# D5035-50.net
KiCad netlist of a schematic drawn in Altium Designer
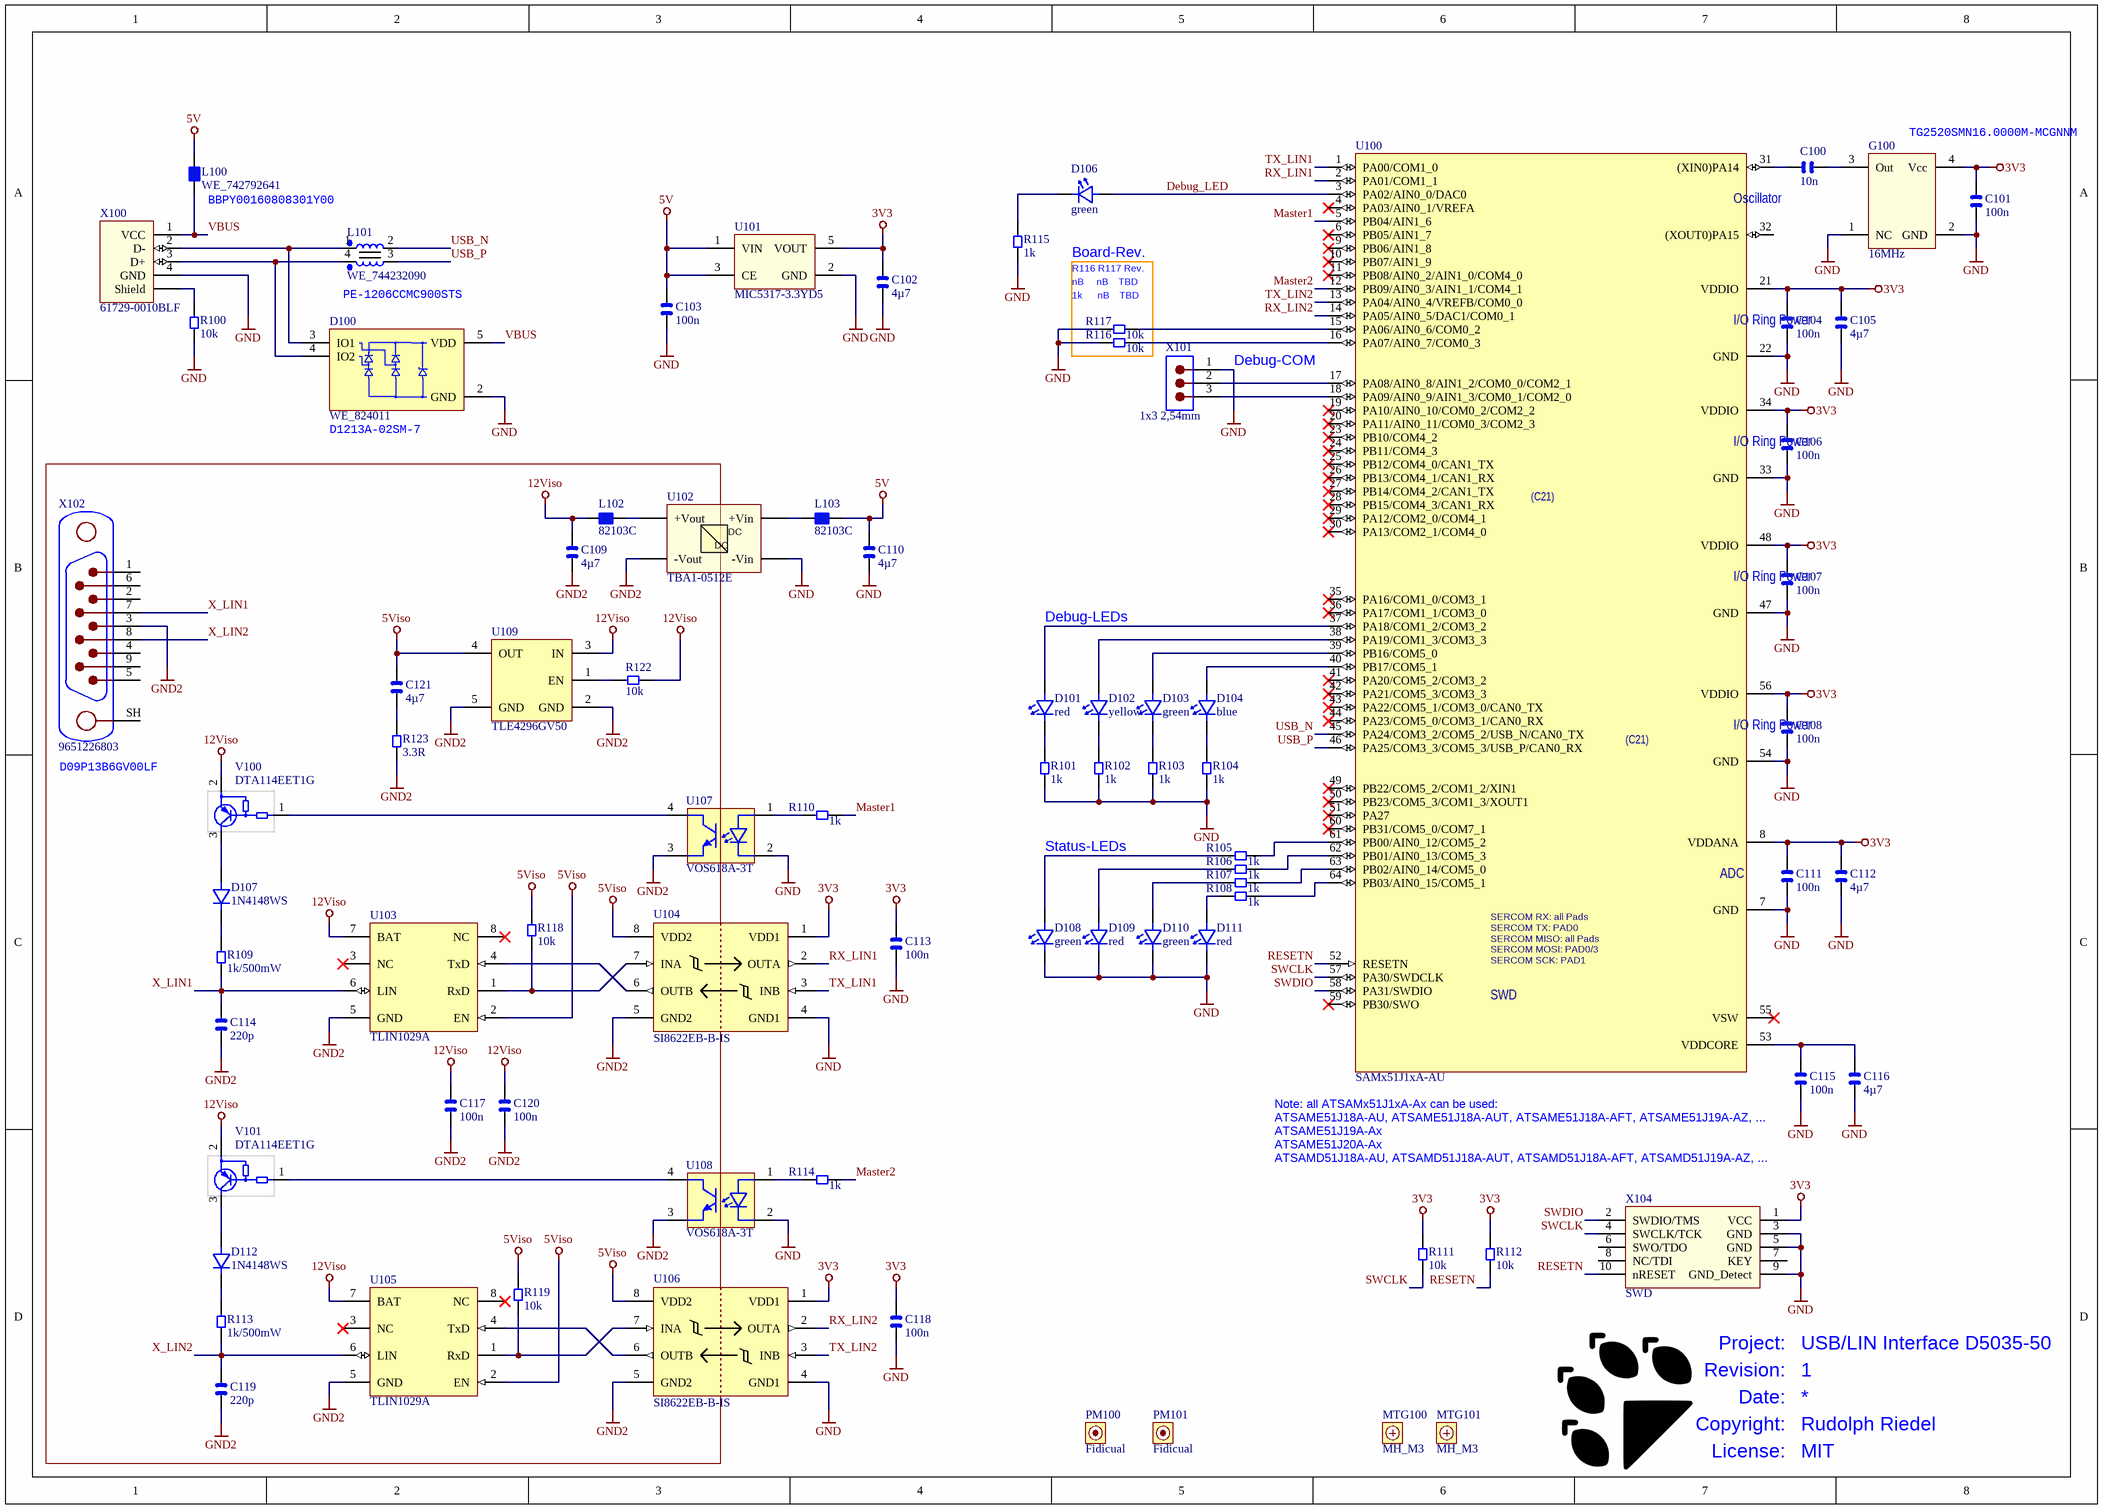
[diagram p0: D5035-50.SchDoc]

(export (version "E")
  (design (tool "Eeschema 10.0.6"))
  (components
    (comp (ref "C100")
      (value "10n")
      (footprint "CAPC1608X09L")
      (description "0603 Chip Capacitor")
      (fields (field (name "PART NUMBER") "CAPC_0603") (field (name "EDITOR") "rriedel"))
      (libsource (lib "HW-Labor_GF") (part "CAP_2_V2"))
    )
    (comp (ref "C101")
      (value "100n")
      (footprint "CAPC1608X09L")
      (description "0603 Chip Capacitor")
      (fields (field (name "PART NUMBER") "CAPC_0603") (field (name "EDITOR") "rriedel"))
      (libsource (lib "HW-Labor_GF") (part "CAP_2_V2"))
    )
    (comp (ref "C102")
      (value "4µ7")
      (footprint "CAPC2012X14L")
      (description "0805 Chip Capacitor")
      (fields (field (name "PART NUMBER") "CAPC_0805") (field (name "EDITOR") "rriedel"))
      (libsource (lib "HW-Labor_GF") (part "CAP_2_V2"))
    )
    (comp (ref "C103")
      (value "100n")
      (footprint "CAPC1608X09L")
      (description "0603 Chip Capacitor")
      (fields (field (name "PART NUMBER") "CAPC_0603") (field (name "EDITOR") "rriedel"))
      (libsource (lib "HW-Labor_GF") (part "CAP_2_V2"))
    )
    (comp (ref "C104")
      (value "100n")
      (footprint "CAPC1608X09L")
      (description "0603 Chip Capacitor")
      (fields (field (name "PART NUMBER") "CAPC_0603") (field (name "EDITOR") "rriedel"))
      (libsource (lib "HW-Labor_GF") (part "CAP_2_V2"))
    )
    (comp (ref "C105")
      (value "4µ7")
      (footprint "CAPC2012X14L")
      (description "0805 Chip Capacitor")
      (fields (field (name "PART NUMBER") "CAPC_0805") (field (name "EDITOR") "rriedel"))
      (libsource (lib "HW-Labor_GF") (part "CAP_2_V2"))
    )
    (comp (ref "C106")
      (value "100n")
      (footprint "CAPC1608X09L")
      (description "0603 Chip Capacitor")
      (fields (field (name "PART NUMBER") "CAPC_0603") (field (name "EDITOR") "rriedel"))
      (libsource (lib "HW-Labor_GF") (part "CAP_2_V2"))
    )
    (comp (ref "C107")
      (value "100n")
      (footprint "CAPC1608X09L")
      (description "0603 Chip Capacitor")
      (fields (field (name "PART NUMBER") "CAPC_0603") (field (name "EDITOR") "rriedel"))
      (libsource (lib "HW-Labor_GF") (part "CAP_2_V2"))
    )
    (comp (ref "C108")
      (value "100n")
      (footprint "CAPC1608X09L")
      (description "0603 Chip Capacitor")
      (fields (field (name "PART NUMBER") "CAPC_0603") (field (name "EDITOR") "rriedel"))
      (libsource (lib "HW-Labor_GF") (part "CAP_2_V2"))
    )
    (comp (ref "C109")
      (value "4µ7")
      (footprint "CAPC2012X14L")
      (description "0805 Chip Capacitor")
      (fields (field (name "PART NUMBER") "CAPC_0805") (field (name "EDITOR") "rriedel"))
      (libsource (lib "HW-Labor_GF") (part "CAP_2_V2"))
    )
    (comp (ref "C110")
      (value "4µ7")
      (footprint "CAPC2012X14L")
      (description "0805 Chip Capacitor")
      (fields (field (name "PART NUMBER") "CAPC_0805") (field (name "EDITOR") "rriedel"))
      (libsource (lib "HW-Labor_GF") (part "CAP_2_V2"))
    )
    (comp (ref "C111")
      (value "100n")
      (footprint "CAPC1608X09L")
      (description "0603 Chip Capacitor")
      (fields (field (name "PART NUMBER") "CAPC_0603") (field (name "EDITOR") "rriedel"))
      (libsource (lib "HW-Labor_GF") (part "CAP_2_V2"))
    )
    (comp (ref "C112")
      (value "4µ7")
      (footprint "CAPC2012X14L")
      (description "0805 Chip Capacitor")
      (fields (field (name "PART NUMBER") "CAPC_0805") (field (name "EDITOR") "rriedel"))
      (libsource (lib "HW-Labor_GF") (part "CAP_2_V2"))
    )
    (comp (ref "C113")
      (value "100n")
      (footprint "CAPC1608X09L")
      (description "0603 Chip Capacitor")
      (fields (field (name "PART NUMBER") "CAPC_0603") (field (name "EDITOR") "rriedel"))
      (libsource (lib "HW-Labor_GF") (part "CAP_2_V2"))
    )
    (comp (ref "C114")
      (value "220p")
      (footprint "CAPC2012X14L")
      (description "0805 Chip Capacitor")
      (fields (field (name "PART NUMBER") "CAPC_0805") (field (name "EDITOR") "rriedel"))
      (libsource (lib "HW-Labor_GF") (part "CAP_2_V2"))
    )
    (comp (ref "C115")
      (value "100n")
      (footprint "CAPC1608X09L")
      (description "0603 Chip Capacitor")
      (fields (field (name "PART NUMBER") "CAPC_0603") (field (name "EDITOR") "rriedel"))
      (libsource (lib "HW-Labor_GF") (part "CAP_2_V2"))
    )
    (comp (ref "C116")
      (value "4µ7")
      (footprint "CAPC2012X14L")
      (description "0805 Chip Capacitor")
      (fields (field (name "PART NUMBER") "CAPC_0805") (field (name "EDITOR") "rriedel"))
      (libsource (lib "HW-Labor_GF") (part "CAP_2_V2"))
    )
    (comp (ref "C117")
      (value "100n")
      (footprint "CAPC1608X09L")
      (description "0603 Chip Capacitor")
      (fields (field (name "PART NUMBER") "CAPC_0603") (field (name "EDITOR") "rriedel"))
      (libsource (lib "HW-Labor_GF") (part "CAP_2_V2"))
    )
    (comp (ref "C118")
      (value "100n")
      (footprint "CAPC1608X09L")
      (description "0603 Chip Capacitor")
      (fields (field (name "PART NUMBER") "CAPC_0603") (field (name "EDITOR") "rriedel"))
      (libsource (lib "HW-Labor_GF") (part "CAP_2_V2"))
    )
    (comp (ref "C119")
      (value "220p")
      (footprint "CAPC2012X14L")
      (description "0805 Chip Capacitor")
      (fields (field (name "PART NUMBER") "CAPC_0805") (field (name "EDITOR") "rriedel"))
      (libsource (lib "HW-Labor_GF") (part "CAP_2_V2"))
    )
    (comp (ref "C120")
      (value "100n")
      (footprint "CAPC1608X09L")
      (description "0603 Chip Capacitor")
      (fields (field (name "PART NUMBER") "CAPC_0603") (field (name "EDITOR") "rriedel"))
      (libsource (lib "HW-Labor_GF") (part "CAP_2_V2"))
    )
    (comp (ref "C121")
      (value "4µ7")
      (footprint "CAPC2012X14L")
      (description "0805 Chip Capacitor")
      (fields (field (name "PART NUMBER") "CAPC_0805") (field (name "EDITOR") "rriedel"))
      (libsource (lib "HW-Labor_GF") (part "CAP_2_V2"))
    )
    (comp (ref "D100")
      (value "WE_824011")
      (footprint "SOT95P280X110-5N")
      (description "TVS Diode Array WE-TVS")
      (fields
        (field (name "MANUFACTURER") "Wuerth")
        (field (name "DISTRIBUTOR_1_PART_NUMBER") "732-4465-1-ND")
        (field (name "EDITOR") "rriedel")
      )
      (libsource (lib "HW-Labor_GF") (part "WE-824011"))
    )
    (comp (ref "D101")
      (value "red")
      (footprint "DIOC1608X06N_LED")
      (description "LED, 0603")
      (fields (field (name "PART NUMBER") "LED_0603") (field (name "EDITOR") "rriedel"))
      (libsource (lib "HW-Labor_GF") (part "LED_generic"))
    )
    (comp (ref "D102")
      (value "yellow")
      (footprint "DIOC1608X06N_LED")
      (description "LED, 0603")
      (fields (field (name "PART NUMBER") "LED_0603") (field (name "EDITOR") "rriedel"))
      (libsource (lib "HW-Labor_GF") (part "LED_generic"))
    )
    (comp (ref "D103")
      (value "green")
      (footprint "DIOC1608X06N_LED")
      (description "LED, 0603")
      (fields (field (name "PART NUMBER") "LED_0603") (field (name "EDITOR") "rriedel"))
      (libsource (lib "HW-Labor_GF") (part "LED_generic"))
    )
    (comp (ref "D104")
      (value "blue")
      (footprint "DIOC1608X06N_LED")
      (description "LED, 0603")
      (fields (field (name "PART NUMBER") "LED_0603") (field (name "EDITOR") "rriedel"))
      (libsource (lib "HW-Labor_GF") (part "LED_generic"))
    )
    (comp (ref "D106")
      (value "green")
      (footprint "DIOC1608X06N_LED")
      (description "LED, 0603")
      (fields (field (name "PART NUMBER") "LED_0603") (field (name "EDITOR") "rriedel"))
      (libsource (lib "HW-Labor_GF") (part "LED_generic"))
    )
    (comp (ref "D107")
      (value "1N4148WS")
      (footprint "SOD323")
      (description "Small Signal Diode IF 0.15A, VR 75V, SOD323F")
      (fields (field (name "DISTRIBUTOR_1_PART_NUMBER") "C2128") (field (name "EDITOR") "rriedel"))
      (libsource (lib "HW-Labor_GF") (part "Diode_A2_K1"))
    )
    (comp (ref "D108")
      (value "green")
      (footprint "DIOC1608X06N_LED")
      (description "LED, 0603")
      (fields (field (name "PART NUMBER") "LED_0603") (field (name "EDITOR") "rriedel"))
      (libsource (lib "HW-Labor_GF") (part "LED_generic"))
    )
    (comp (ref "D109")
      (value "red")
      (footprint "DIOC1608X06N_LED")
      (description "LED, 0603")
      (fields (field (name "PART NUMBER") "LED_0603") (field (name "EDITOR") "rriedel"))
      (libsource (lib "HW-Labor_GF") (part "LED_generic"))
    )
    (comp (ref "D110")
      (value "green")
      (footprint "DIOC1608X06N_LED")
      (description "LED, 0603")
      (fields (field (name "PART NUMBER") "LED_0603") (field (name "EDITOR") "rriedel"))
      (libsource (lib "HW-Labor_GF") (part "LED_generic"))
    )
    (comp (ref "D111")
      (value "red")
      (footprint "DIOC1608X06N_LED")
      (description "LED, 0603")
      (fields (field (name "PART NUMBER") "LED_0603") (field (name "EDITOR") "rriedel"))
      (libsource (lib "HW-Labor_GF") (part "LED_generic"))
    )
    (comp (ref "D112")
      (value "1N4148WS")
      (footprint "SOD323")
      (description "Small Signal Diode IF 0.15A, VR 75V, SOD323F")
      (fields (field (name "DISTRIBUTOR_1_PART_NUMBER") "C2128") (field (name "EDITOR") "rriedel"))
      (libsource (lib "HW-Labor_GF") (part "Diode_A2_K1"))
    )
    (comp (ref "G100")
      (value "16MHz")
      (footprint "TG2520")
      (description "16MHz Oscillator, +/- 0.5ppm")
      (fields
        (field (name "PART NUMBER") "TG2520SMN16.0000M-MCGNNM")
        (field (name "MANUFACTURER") "Epson")
        (field (name "EDITOR") "rriedel")
      )
      (libsource (lib "HW-Labor_GF") (part "TG2520"))
    )
    (comp (ref "L100")
      (value "WE_742792641")
      (footprint "INDC1608X06L")
      (description "SMT EMI suppression ferrite bead WE-CBF")
      (fields
        (field (name "MANUFACTURER") "Wuerth")
        (field (name "DISTRIBUTOR_1_PART_NUMBER") "732-1592-1-ND")
        (field (name "EDITOR") "rriedel")
      )
      (libsource (lib "HW-Labor_GF") (part "IND_2_V1"))
    )
    (comp (ref "L101")
      (value "WE_744232090")
      (footprint "WE_744232090")
      (description "SMD common mode noise suppressor WE-CNSW")
      (fields
        (field (name "MANUFACTURER") "Wuerth")
        (field (name "DISTRIBUTOR_1_PART_NUMBER") "732-1469-1-ND")
        (field (name "EDITOR") "rriedel")
      )
      (libsource (lib "HW-Labor_GF") (part "WE_744232090"))
    )
    (comp (ref "L102")
      (value "82103C")
      (footprint "Murata_8200C")
      (description "10µH, 0,5A, 400mR")
      (fields
        (field (name "MANUFACTURER") "Murata")
        (field (name "DISTRIBUTOR_1_PART_NUMBER") "811-2473-1-ND")
        (field (name "EDITOR") "rriedel")
      )
      (libsource (lib "HW-Labor_GF") (part "IND_2_V1"))
    )
    (comp (ref "L103")
      (value "82103C")
      (footprint "Murata_8200C")
      (description "10µH, 0,5A, 400mR")
      (fields
        (field (name "MANUFACTURER") "Murata")
        (field (name "DISTRIBUTOR_1_PART_NUMBER") "811-2473-1-ND")
        (field (name "EDITOR") "rriedel")
      )
      (libsource (lib "HW-Labor_GF") (part "IND_2_V1"))
    )
    (comp (ref "MTG100")
      (value "MH_M3")
      (footprint "HOLE_3_2MM")
      (description "Mounting-Hole for M3 screws")
      (fields (field (name "EDITOR") "rriedel"))
      (libsource (lib "HW-Labor_GF") (part "MTG_V1"))
    )
    (comp (ref "MTG101")
      (value "MH_M3")
      (footprint "HOLE_3_2MM")
      (description "Mounting-Hole for M3 screws")
      (fields (field (name "EDITOR") "rriedel"))
      (libsource (lib "HW-Labor_GF") (part "MTG_V1"))
    )
    (comp (ref "PM100")
      (value "Fidicual")
      (footprint "PM100")
      (fields (field (name "PART NUMBER") "PM100") (field (name "EDITOR") "rriedel"))
      (libsource (lib "HW-Labor_GF") (part "PM100"))
    )
    (comp (ref "PM101")
      (value "Fidicual")
      (footprint "PM100")
      (fields (field (name "PART NUMBER") "PM100") (field (name "EDITOR") "rriedel"))
      (libsource (lib "HW-Labor_GF") (part "PM100"))
    )
    (comp (ref "R100")
      (value "10k")
      (footprint "RESC1608X06L")
      (description "0603 Chip Resistor")
      (fields (field (name "PART NUMBER") "RESC_0603") (field (name "EDITOR") "rriedel"))
      (libsource (lib "HW-Labor_GF") (part "RES_2_V2"))
    )
    (comp (ref "R101")
      (value "1k")
      (footprint "RESC1608X06L")
      (description "0603 Chip Resistor")
      (fields (field (name "PART NUMBER") "RESC_0603") (field (name "EDITOR") "rriedel"))
      (libsource (lib "HW-Labor_GF") (part "RES_2_V2"))
    )
    (comp (ref "R102")
      (value "1k")
      (footprint "RESC1608X06L")
      (description "0603 Chip Resistor")
      (fields (field (name "PART NUMBER") "RESC_0603") (field (name "EDITOR") "rriedel"))
      (libsource (lib "HW-Labor_GF") (part "RES_2_V2"))
    )
    (comp (ref "R103")
      (value "1k")
      (footprint "RESC1608X06L")
      (description "0603 Chip Resistor")
      (fields (field (name "PART NUMBER") "RESC_0603") (field (name "EDITOR") "rriedel"))
      (libsource (lib "HW-Labor_GF") (part "RES_2_V2"))
    )
    (comp (ref "R104")
      (value "1k")
      (footprint "RESC1608X06L")
      (description "0603 Chip Resistor")
      (fields (field (name "PART NUMBER") "RESC_0603") (field (name "EDITOR") "rriedel"))
      (libsource (lib "HW-Labor_GF") (part "RES_2_V2"))
    )
    (comp (ref "R105")
      (value "1k")
      (footprint "RESC1608X06L")
      (description "0603 Chip Resistor")
      (fields (field (name "PART NUMBER") "RESC_0603") (field (name "EDITOR") "rriedel"))
      (libsource (lib "HW-Labor_GF") (part "RES_2_V2"))
    )
    (comp (ref "R106")
      (value "1k")
      (footprint "RESC1608X06L")
      (description "0603 Chip Resistor")
      (fields (field (name "PART NUMBER") "RESC_0603") (field (name "EDITOR") "rriedel"))
      (libsource (lib "HW-Labor_GF") (part "RES_2_V2"))
    )
    (comp (ref "R107")
      (value "1k")
      (footprint "RESC1608X06L")
      (description "0603 Chip Resistor")
      (fields (field (name "PART NUMBER") "RESC_0603") (field (name "EDITOR") "rriedel"))
      (libsource (lib "HW-Labor_GF") (part "RES_2_V2"))
    )
    (comp (ref "R108")
      (value "1k")
      (footprint "RESC1608X06L")
      (description "0603 Chip Resistor")
      (fields (field (name "PART NUMBER") "RESC_0603") (field (name "EDITOR") "rriedel"))
      (libsource (lib "HW-Labor_GF") (part "RES_2_V2"))
    )
    (comp (ref "R109")
      (value "1k/500mW")
      (footprint "RESC2012X06L")
      (description "0805 Chip Resistor")
      (fields (field (name "PART NUMBER") "RESC_0805") (field (name "EDITOR") "rriedel"))
      (libsource (lib "HW-Labor_GF") (part "RES_2_V2"))
    )
    (comp (ref "R110")
      (value "1k")
      (footprint "RESC1608X06L")
      (description "0603 Chip Resistor")
      (fields (field (name "PART NUMBER") "RESC_0603") (field (name "EDITOR") "rriedel"))
      (libsource (lib "HW-Labor_GF") (part "RES_2_V2"))
    )
    (comp (ref "R111")
      (value "10k")
      (footprint "RESC1608X06L")
      (description "0603 Chip Resistor")
      (fields (field (name "PART NUMBER") "RESC_0603") (field (name "EDITOR") "rriedel"))
      (libsource (lib "HW-Labor_GF") (part "RES_2_V2"))
    )
    (comp (ref "R112")
      (value "10k")
      (footprint "RESC1608X06L")
      (description "0603 Chip Resistor")
      (fields (field (name "PART NUMBER") "RESC_0603") (field (name "EDITOR") "rriedel"))
      (libsource (lib "HW-Labor_GF") (part "RES_2_V2"))
    )
    (comp (ref "R113")
      (value "1k/500mW")
      (footprint "RESC2012X06L")
      (description "0805 Chip Resistor")
      (fields (field (name "PART NUMBER") "RESC_0805") (field (name "EDITOR") "rriedel"))
      (libsource (lib "HW-Labor_GF") (part "RES_2_V2"))
    )
    (comp (ref "R114")
      (value "1k")
      (footprint "RESC1608X06L")
      (description "0603 Chip Resistor")
      (fields (field (name "PART NUMBER") "RESC_0603") (field (name "EDITOR") "rriedel"))
      (libsource (lib "HW-Labor_GF") (part "RES_2_V2"))
    )
    (comp (ref "R115")
      (value "1k")
      (footprint "RESC1608X06L")
      (description "0603 Chip Resistor")
      (fields (field (name "PART NUMBER") "RESC_0603") (field (name "EDITOR") "rriedel"))
      (libsource (lib "HW-Labor_GF") (part "RES_2_V2"))
    )
    (comp (ref "R116")
      (value "10k")
      (footprint "RESC1608X06L")
      (description "0603 Chip Resistor")
      (fields (field (name "PART NUMBER") "RESC_0603") (field (name "EDITOR") "rriedel"))
      (libsource (lib "HW-Labor_GF") (part "RES_2_V2"))
    )
    (comp (ref "R117")
      (value "10k")
      (footprint "RESC1608X06L")
      (description "0603 Chip Resistor")
      (fields (field (name "PART NUMBER") "RESC_0603") (field (name "EDITOR") "rriedel"))
      (libsource (lib "HW-Labor_GF") (part "RES_2_V2"))
    )
    (comp (ref "R118")
      (value "10k")
      (footprint "RESC1608X06L")
      (description "0603 Chip Resistor")
      (fields (field (name "PART NUMBER") "RESC_0603") (field (name "EDITOR") "rriedel"))
      (libsource (lib "HW-Labor_GF") (part "RES_2_V2"))
    )
    (comp (ref "R119")
      (value "10k")
      (footprint "RESC1608X06L")
      (description "0603 Chip Resistor")
      (fields (field (name "PART NUMBER") "RESC_0603") (field (name "EDITOR") "rriedel"))
      (libsource (lib "HW-Labor_GF") (part "RES_2_V2"))
    )
    (comp (ref "R122")
      (value "10k")
      (footprint "RESC1608X06L")
      (description "0603 Chip Resistor")
      (fields (field (name "PART NUMBER") "RESC_0603") (field (name "EDITOR") "rriedel"))
      (libsource (lib "HW-Labor_GF") (part "RES_2_V2"))
    )
    (comp (ref "R123")
      (value "3.3R")
      (footprint "RESC1608X06L")
      (description "0603 Chip Resistor")
      (fields (field (name "PART NUMBER") "RESC_0603") (field (name "EDITOR") "rriedel"))
      (libsource (lib "HW-Labor_GF") (part "RES_2_V2"))
    )
    (comp (ref "U100")
      (value "SAMx51J1xA-AU")
      (footprint "TSQFP50P1200X1200X120-64N")
      (description "32-bit Microcontroller, 120MHz Cortex M4-F, 512k FLASH,  2x CAN-FD, -40…85°C")
      (fields
        (field (name "PART NUMBER") "SAME51J19A-AU")
        (field (name "MANUFACTURER") "Microchip")
        (field (name "EDITOR") "rriedel")
      )
      (libsource (lib "HW-Labor_GF") (part "SAME5xJxxA-AUx"))
    )
    (comp (ref "U101")
      (value "MIC5317-3.3YD5")
      (footprint "SOT95P280X110-5N")
      (description "100 mA LDO,  Vout= 3,3V, -40°C..125°C")
      (fields
        (field (name "PART NUMBER") "MIC5233-3.3")
        (field (name "MANUFACTURER") "Microchip")
        (field (name "EDITOR") "rriedel")
      )
      (libsource (lib "HW-Labor_GF") (part "LDO_SOT23-5"))
    )
    (comp (ref "U102")
      (value "TBA1-0512E")
      (footprint "MER1SxxxxC")
      (description "Isolated 1W Single Output DC-DC Converters 5V/12V 84mA")
      (fields
        (field (name "PART NUMBER") "MER1S0505SC")
        (field (name "MANUFACTURER") "Murata")
        (field (name "EDITOR") "rriedel")
      )
      (libsource (lib "HW-Labor_GF") (part "MER1SxxxxC"))
    )
    (comp (ref "U103")
      (value "TLIN1029A")
      (footprint "SOIC127P600X175-8N")
      (description "LIN transceiver")
      (fields
        (field (name "MANUFACTURER") "TI")
        (field (name "DISTRIBUTOR_1_PART_NUMBER") "595-TLIN1029ADRQ1")
        (field (name "EDITOR") "rriedel")
      )
      (libsource (lib "HW-Labor_GF") (part "TLIN1029A"))
    )
    (comp (ref "U104")
      (value "SI8622EB-B-IS")
      (footprint "SOIC127P600X175-8N")
      (description "Dual channel digital isolator, 150Mbit, 2,5kV")
      (fields
        (field (name "MANUFACTURER") "Silicon Labs")
        (field (name "DISTRIBUTOR_1_PART_NUMBER") "336-5209-1-ND")
        (field (name "EDITOR") "rriedel")
      )
      (libsource (lib "HW-Labor_GF") (part "SI8622"))
    )
    (comp (ref "U105")
      (value "TLIN1029A")
      (footprint "SOIC127P600X175-8N")
      (description "LIN transceiver")
      (fields
        (field (name "MANUFACTURER") "TI")
        (field (name "DISTRIBUTOR_1_PART_NUMBER") "595-TLIN1029ADRQ1")
        (field (name "EDITOR") "rriedel")
      )
      (libsource (lib "HW-Labor_GF") (part "TLIN1029A"))
    )
    (comp (ref "U106")
      (value "SI8622EB-B-IS")
      (footprint "SOIC127P600X175-8N")
      (description "Dual channel digital isolator, 150Mbit, 2,5kV")
      (fields
        (field (name "MANUFACTURER") "Silicon Labs")
        (field (name "DISTRIBUTOR_1_PART_NUMBER") "336-5209-1-ND")
        (field (name "EDITOR") "rriedel")
      )
      (libsource (lib "HW-Labor_GF") (part "SI8622"))
    )
    (comp (ref "U107")
      (value "VOS618A-3T")
      (footprint "SSOP-4")
      (description "Optocoupler, Phototransistor Output, Low Input Current, SSOP-4")
      (fields
        (field (name "MANUFACTURER") "Vishay")
        (field (name "DISTRIBUTOR_1_PART_NUMBER") "VOS618A-3TCT-ND‎")
        (field (name "EDITOR") "rriedel")
      )
      (libsource (lib "HW-Labor_GF") (part "VOS618A"))
    )
    (comp (ref "U108")
      (value "VOS618A-3T")
      (footprint "SSOP-4")
      (description "Optocoupler, Phototransistor Output, Low Input Current, SSOP-4")
      (fields
        (field (name "MANUFACTURER") "Vishay")
        (field (name "DISTRIBUTOR_1_PART_NUMBER") "VOS618A-3TCT-ND‎")
        (field (name "EDITOR") "rriedel")
      )
      (libsource (lib "HW-Labor_GF") (part "VOS618A"))
    )
    (comp (ref "U109")
      (value "TLE4296GV50")
      (footprint "INF-PG-SCT595V")
      (description "30 mA LDO, Vout = 5,0V, 4%")
      (fields (field (name "MANUFACTURER") "Infineon") (field (name "EDITOR") "rriedel"))
      (libsource (lib "HW-Labor_GF") (part "TLE4295GVxx"))
    )
    (comp (ref "V100")
      (value "DTA114EET1G")
      (footprint "SOT50P162X60-3N")
      (description "PNP Transistor with Resistors (10kΩ, 10kΩ)  VCE= 50V, IC=100mA, SOT23, AEC Q101")
      (fields (field (name "EDITOR") "rriedel"))
      (libsource (lib "HW-Labor_GF") (part "PNP_Digital"))
    )
    (comp (ref "V101")
      (value "DTA114EET1G")
      (footprint "SOT50P162X60-3N")
      (description "PNP Transistor with Resistors (10kΩ, 10kΩ)  VCE= 50V, IC=100mA, SOT23, AEC Q101")
      (fields (field (name "EDITOR") "rriedel"))
      (libsource (lib "HW-Labor_GF") (part "PNP_Digital"))
    )
    (comp (ref "X100")
      (value "61729-0010BLF")
      (footprint "61729-xxxxxLF")
      (description "USB-B socket, THT")
      (fields
        (field (name "MANUFACTURER") "Amphenol")
        (field (name "DISTRIBUTOR_1_PART_NUMBER") "609-1039-ND")
        (field (name "EDITOR") "rriedel")
      )
      (libsource (lib "HW-Labor_GF") (part "USB"))
    )
    (comp (ref "X101")
      (value "1x3 2,54mm")
      (footprint "PINH_1x03_2_54mm")
      (description "Pin-Header 2,54 mm 3pins")
      (fields (field (name "PART NUMBER") "PINH_1x3_2_54") (field (name "EDITOR") "rriedel"))
      (libsource (lib "HW-Labor_GF") (part "CONM_1x3_V2"))
    )
    (comp (ref "X102")
      (value "9651226803")
      (footprint "09651226803")
      (description "D-Sub, 9 pin, male, right angle")
      (fields
        (field (name "MANUFACTURER") "Harting")
        (field (name "DISTRIBUTOR_1_PART_NUMBER") "2752007")
        (field (name "EDITOR") "rriedel")
      )
      (libsource (lib "HW-Labor_GF") (part "D_Sub_9_Male"))
    )
    (comp (ref "X104")
      (value "SWD")
      (footprint "FTSH-105-01-L-DV-K")
      (description "ARM Debug-Header 2x5 1,27 mm")
      (fields (field (name "EDITOR") "rriedel"))
      (libsource (lib "HW-Labor_GF") (part "SWD"))
    )
  )
  (nets
    (net (code "1") (name "/Debug_LED") (class "Default")
      (node (ref "D106") (pin "2") (pinfunction "2_2") (pintype "passive"))
      (node (ref "U100") (pin "3") (pinfunction "PA02/AIN0_0/DAC0_3") (pintype "bidirectional"))
    )
    (net (code "2") (name "/Master1") (class "Default")
      (node (ref "R110") (pin "1") (pinfunction "1_1") (pintype "passive"))
      (node (ref "U100") (pin "5") (pinfunction "PB04/AIN1_6_5") (pintype "bidirectional"))
    )
    (net (code "3") (name "/Master2") (class "Default")
      (node (ref "R114") (pin "1") (pinfunction "1_1") (pintype "passive"))
      (node (ref "U100") (pin "12") (pinfunction "PB09/AIN0_3/AIN1_1/COM4_1_12") (pintype "bidirectional"))
    )
    (net (code "4") (name "/RESETN") (class "Default")
      (node (ref "R112") (pin "2") (pinfunction "2_2") (pintype "passive"))
      (node (ref "U100") (pin "52") (pinfunction "RESETN_52") (pintype "input"))
      (node (ref "X104") (pin "10") (pinfunction "nRESET_10") (pintype "passive"))
    )
    (net (code "5") (name "/RX_LIN1") (class "Default")
      (node (ref "U100") (pin "2") (pinfunction "PA01/COM1_1_2") (pintype "bidirectional"))
      (node (ref "U104") (pin "2") (pinfunction "OUTA_2") (pintype "output"))
    )
    (net (code "6") (name "/RX_LIN2") (class "Default")
      (node (ref "U100") (pin "14") (pinfunction "PA05/AIN0_5/DAC1/COM0_1_14") (pintype "bidirectional"))
      (node (ref "U106") (pin "2") (pinfunction "OUTA_2") (pintype "output"))
    )
    (net (code "7") (name "/SWCLK") (class "Default")
      (node (ref "R111") (pin "2") (pinfunction "2_2") (pintype "passive"))
      (node (ref "U100") (pin "57") (pinfunction "PA30/SWDCLK_57") (pintype "bidirectional"))
      (node (ref "X104") (pin "4") (pinfunction "SWCLK/TCK_4") (pintype "passive"))
    )
    (net (code "8") (name "/SWDIO") (class "Default")
      (node (ref "U100") (pin "58") (pinfunction "PA31/SWDIO_58") (pintype "bidirectional"))
      (node (ref "X104") (pin "2") (pinfunction "SWDIO/TMS_2") (pintype "passive"))
    )
    (net (code "9") (name "/TX_LIN1") (class "Default")
      (node (ref "U100") (pin "1") (pinfunction "PA00/COM1_0_1") (pintype "bidirectional"))
      (node (ref "U104") (pin "3") (pinfunction "INB_3") (pintype "input"))
    )
    (net (code "10") (name "/TX_LIN2") (class "Default")
      (node (ref "U100") (pin "13") (pinfunction "PA04/AIN0_4/VREFB/COM0_0_13") (pintype "bidirectional"))
      (node (ref "U106") (pin "3") (pinfunction "INB_3") (pintype "input"))
    )
    (net (code "11") (name "/USB_N") (class "Default")
      (node (ref "L101") (pin "2") (pinfunction "2_2") (pintype "passive"))
      (node (ref "U100") (pin "45") (pinfunction "PA24/COM3_2/COM5_2/USB_N/CAN0_TX_45") (pintype "bidirectional"))
    )
    (net (code "12") (name "/USB_P") (class "Default")
      (node (ref "L101") (pin "3") (pinfunction "3_3") (pintype "passive"))
      (node (ref "U100") (pin "46") (pinfunction "PA25/COM3_3/COM5_3/USB_P/CAN0_RX_46") (pintype "bidirectional"))
    )
    (net (code "13") (name "/VBUS") (class "Default")
      (node (ref "D100") (pin "5") (pinfunction "VDD_5") (pintype "passive"))
      (node (ref "L100") (pin "1") (pinfunction "1_1") (pintype "passive"))
      (node (ref "X100") (pin "1") (pinfunction "VCC_1") (pintype "power_in"))
    )
    (net (code "14") (name "/X_LIN1") (class "Default")
      (node (ref "C114") (pin "2") (pinfunction "2_2") (pintype "passive"))
      (node (ref "R109") (pin "1") (pinfunction "1_1") (pintype "passive"))
      (node (ref "U103") (pin "6") (pinfunction "LIN_6") (pintype "bidirectional"))
      (node (ref "X102") (pin "7") (pinfunction "7_7") (pintype "passive"))
    )
    (net (code "15") (name "/X_LIN2") (class "Default")
      (node (ref "C119") (pin "2") (pinfunction "2_2") (pintype "passive"))
      (node (ref "R113") (pin "1") (pinfunction "1_1") (pintype "passive"))
      (node (ref "U105") (pin "6") (pinfunction "LIN_6") (pintype "bidirectional"))
      (node (ref "X102") (pin "8") (pinfunction "8_8") (pintype "passive"))
    )
    (net (code "16") (name "3V3") (class "Default")
      (node (ref "C101") (pin "2") (pinfunction "2_2") (pintype "passive"))
      (node (ref "C102") (pin "2") (pinfunction "2_2") (pintype "passive"))
      (node (ref "C104") (pin "2") (pinfunction "2_2") (pintype "passive"))
      (node (ref "C105") (pin "2") (pinfunction "2_2") (pintype "passive"))
      (node (ref "C106") (pin "2") (pinfunction "2_2") (pintype "passive"))
      (node (ref "C107") (pin "2") (pinfunction "2_2") (pintype "passive"))
      (node (ref "C108") (pin "2") (pinfunction "2_2") (pintype "passive"))
      (node (ref "C111") (pin "2") (pinfunction "2_2") (pintype "passive"))
      (node (ref "C112") (pin "2") (pinfunction "2_2") (pintype "passive"))
      (node (ref "C113") (pin "2") (pinfunction "2_2") (pintype "passive"))
      (node (ref "C118") (pin "2") (pinfunction "2_2") (pintype "passive"))
      (node (ref "G100") (pin "4") (pinfunction "Vcc_4") (pintype "passive"))
      (node (ref "R111") (pin "1") (pinfunction "1_1") (pintype "passive"))
      (node (ref "R112") (pin "1") (pinfunction "1_1") (pintype "passive"))
      (node (ref "U100") (pin "21") (pinfunction "VDDIO_21") (pintype "power_in"))
      (node (ref "U100") (pin "34") (pinfunction "VDDIO_34") (pintype "power_in"))
      (node (ref "U100") (pin "48") (pinfunction "VDDIO_48") (pintype "power_in"))
      (node (ref "U100") (pin "56") (pinfunction "VDDIO_56") (pintype "power_in"))
      (node (ref "U100") (pin "8") (pinfunction "VDDANA_8") (pintype "power_in"))
      (node (ref "U101") (pin "5") (pinfunction "VOUT_5") (pintype "passive"))
      (node (ref "U104") (pin "1") (pinfunction "VDD1_1") (pintype "power_in"))
      (node (ref "U106") (pin "1") (pinfunction "VDD1_1") (pintype "power_in"))
      (node (ref "X104") (pin "1") (pinfunction "VCC_1") (pintype "power_in"))
    )
    (net (code "17") (name "5V") (class "Default")
      (node (ref "C103") (pin "2") (pinfunction "2_2") (pintype "passive"))
      (node (ref "C110") (pin "2") (pinfunction "2_2") (pintype "passive"))
      (node (ref "L100") (pin "2") (pinfunction "2_2") (pintype "passive"))
      (node (ref "L103") (pin "1") (pinfunction "1_1") (pintype "passive"))
      (node (ref "U101") (pin "1") (pinfunction "VIN_1") (pintype "passive"))
      (node (ref "U101") (pin "3") (pinfunction "CE_3") (pintype "passive"))
    )
    (net (code "18") (name "5Viso") (class "Default")
      (node (ref "C121") (pin "2") (pinfunction "2_2") (pintype "passive"))
      (node (ref "R118") (pin "1") (pinfunction "1_1") (pintype "passive"))
      (node (ref "R119") (pin "1") (pinfunction "1_1") (pintype "passive"))
      (node (ref "U103") (pin "2") (pinfunction "EN_2") (pintype "input"))
      (node (ref "U104") (pin "8") (pinfunction "VDD2_8") (pintype "power_in"))
      (node (ref "U105") (pin "2") (pinfunction "EN_2") (pintype "input"))
      (node (ref "U106") (pin "8") (pinfunction "VDD2_8") (pintype "power_in"))
      (node (ref "U109") (pin "4") (pinfunction "OUT_4") (pintype "passive"))
    )
    (net (code "19") (name "12Viso") (class "Default")
      (node (ref "C109") (pin "2") (pinfunction "2_2") (pintype "passive"))
      (node (ref "C117") (pin "2") (pinfunction "2_2") (pintype "passive"))
      (node (ref "C120") (pin "2") (pinfunction "2_2") (pintype "passive"))
      (node (ref "L102") (pin "2") (pinfunction "2_2") (pintype "passive"))
      (node (ref "R122") (pin "2") (pinfunction "2_2") (pintype "passive"))
      (node (ref "U103") (pin "7") (pinfunction "BAT_7") (pintype "power_in"))
      (node (ref "U105") (pin "7") (pinfunction "BAT_7") (pintype "power_in"))
      (node (ref "U109") (pin "3") (pinfunction "IN_3") (pintype "passive"))
      (node (ref "V100") (pin "2") (pinfunction "2_2") (pintype "passive"))
      (node (ref "V101") (pin "2") (pinfunction "2_2") (pintype "passive"))
    )
    (net (code "20") (name "GND") (class "Default")
      (node (ref "C101") (pin "1") (pinfunction "1_1") (pintype "passive"))
      (node (ref "C102") (pin "1") (pinfunction "1_1") (pintype "passive"))
      (node (ref "C103") (pin "1") (pinfunction "1_1") (pintype "passive"))
      (node (ref "C104") (pin "1") (pinfunction "1_1") (pintype "passive"))
      (node (ref "C105") (pin "1") (pinfunction "1_1") (pintype "passive"))
      (node (ref "C106") (pin "1") (pinfunction "1_1") (pintype "passive"))
      (node (ref "C107") (pin "1") (pinfunction "1_1") (pintype "passive"))
      (node (ref "C108") (pin "1") (pinfunction "1_1") (pintype "passive"))
      (node (ref "C110") (pin "1") (pinfunction "1_1") (pintype "passive"))
      (node (ref "C111") (pin "1") (pinfunction "1_1") (pintype "passive"))
      (node (ref "C112") (pin "1") (pinfunction "1_1") (pintype "passive"))
      (node (ref "C113") (pin "1") (pinfunction "1_1") (pintype "passive"))
      (node (ref "C115") (pin "1") (pinfunction "1_1") (pintype "passive"))
      (node (ref "C116") (pin "1") (pinfunction "1_1") (pintype "passive"))
      (node (ref "C118") (pin "1") (pinfunction "1_1") (pintype "passive"))
      (node (ref "D100") (pin "2") (pinfunction "GND_2") (pintype "passive"))
      (node (ref "D108") (pin "1") (pinfunction "1_1") (pintype "passive"))
      (node (ref "D109") (pin "1") (pinfunction "1_1") (pintype "passive"))
      (node (ref "D110") (pin "1") (pinfunction "1_1") (pintype "passive"))
      (node (ref "D111") (pin "1") (pinfunction "1_1") (pintype "passive"))
      (node (ref "G100") (pin "1") (pinfunction "NC_1") (pintype "passive"))
      (node (ref "G100") (pin "2") (pinfunction "GND_2") (pintype "power_in"))
      (node (ref "R100") (pin "1") (pinfunction "1_1") (pintype "passive"))
      (node (ref "R101") (pin "1") (pinfunction "1_1") (pintype "passive"))
      (node (ref "R102") (pin "1") (pinfunction "1_1") (pintype "passive"))
      (node (ref "R103") (pin "1") (pinfunction "1_1") (pintype "passive"))
      (node (ref "R104") (pin "1") (pinfunction "1_1") (pintype "passive"))
      (node (ref "R115") (pin "1") (pinfunction "1_1") (pintype "passive"))
      (node (ref "R116") (pin "2") (pinfunction "2_2") (pintype "passive"))
      (node (ref "R117") (pin "2") (pinfunction "2_2") (pintype "passive"))
      (node (ref "U100") (pin "22") (pinfunction "GND_22") (pintype "power_in"))
      (node (ref "U100") (pin "33") (pinfunction "GND_33") (pintype "power_in"))
      (node (ref "U100") (pin "47") (pinfunction "GND_47") (pintype "power_in"))
      (node (ref "U100") (pin "54") (pinfunction "GND_54") (pintype "power_in"))
      (node (ref "U100") (pin "7") (pinfunction "GND_7") (pintype "power_in"))
      (node (ref "U101") (pin "2") (pinfunction "GND_2") (pintype "passive"))
      (node (ref "U102") (pin "2") (pinfunction "-Vin_2") (pintype "power_in"))
      (node (ref "U104") (pin "4") (pinfunction "GND1_4") (pintype "power_in"))
      (node (ref "U106") (pin "4") (pinfunction "GND1_4") (pintype "power_in"))
      (node (ref "U107") (pin "2") (pinfunction "C_2") (pintype "passive"))
      (node (ref "U108") (pin "2") (pinfunction "C_2") (pintype "passive"))
      (node (ref "X100") (pin "4") (pinfunction "GND_4") (pintype "power_in"))
      (node (ref "X101") (pin "1") (pinfunction "1_1") (pintype "passive"))
      (node (ref "X104") (pin "3") (pinfunction "GND_3") (pintype "power_in"))
      (node (ref "X104") (pin "5") (pinfunction "GND_5") (pintype "power_in"))
      (node (ref "X104") (pin "9") (pinfunction "GND_Detect_9") (pintype "power_in"))
    )
    (net (code "21") (name "GND2") (class "Default")
      (node (ref "C109") (pin "1") (pinfunction "1_1") (pintype "passive"))
      (node (ref "C114") (pin "1") (pinfunction "1_1") (pintype "passive"))
      (node (ref "C117") (pin "1") (pinfunction "1_1") (pintype "passive"))
      (node (ref "C119") (pin "1") (pinfunction "1_1") (pintype "passive"))
      (node (ref "C120") (pin "1") (pinfunction "1_1") (pintype "passive"))
      (node (ref "R123") (pin "2") (pinfunction "2_2") (pintype "passive"))
      (node (ref "U102") (pin "4") (pinfunction "-Vout_4") (pintype "power_in"))
      (node (ref "U103") (pin "5") (pinfunction "GND_5") (pintype "power_in"))
      (node (ref "U104") (pin "5") (pinfunction "GND2_5") (pintype "power_in"))
      (node (ref "U105") (pin "5") (pinfunction "GND_5") (pintype "power_in"))
      (node (ref "U106") (pin "5") (pinfunction "GND2_5") (pintype "power_in"))
      (node (ref "U107") (pin "3") (pinfunction "E_3") (pintype "passive"))
      (node (ref "U108") (pin "3") (pinfunction "E_3") (pintype "passive"))
      (node (ref "U109") (pin "2") (pinfunction "GND_2") (pintype "passive"))
      (node (ref "U109") (pin "5") (pinfunction "GND_5") (pintype "passive"))
      (node (ref "X102") (pin "3") (pinfunction "3_3") (pintype "passive"))
    )
    (net (code "22") (name "Net-(C121-Pad1)") (class "Default")
      (node (ref "C121") (pin "1") (pinfunction "1_1") (pintype "passive"))
      (node (ref "R123") (pin "1") (pinfunction "1_1") (pintype "passive"))
    )
    (net (code "23") (name "Net-(D100-IO1)") (class "Default")
      (node (ref "D100") (pin "3") (pinfunction "IO1_3") (pintype "passive"))
      (node (ref "L101") (pin "1") (pinfunction "1_1") (pintype "passive"))
      (node (ref "X100") (pin "2") (pinfunction "D-_2") (pintype "bidirectional"))
    )
    (net (code "24") (name "Net-(D100-IO2)") (class "Default")
      (node (ref "D100") (pin "4") (pinfunction "IO2_4") (pintype "passive"))
      (node (ref "L101") (pin "4") (pinfunction "4_4") (pintype "passive"))
      (node (ref "X100") (pin "3") (pinfunction "D+_3") (pintype "bidirectional"))
    )
    (net (code "25") (name "Net-(D101-Pad1)") (class "Default")
      (node (ref "D101") (pin "1") (pinfunction "1_1") (pintype "passive"))
      (node (ref "R101") (pin "2") (pinfunction "2_2") (pintype "passive"))
    )
    (net (code "26") (name "Net-(D102-Pad1)") (class "Default")
      (node (ref "D102") (pin "1") (pinfunction "1_1") (pintype "passive"))
      (node (ref "R102") (pin "2") (pinfunction "2_2") (pintype "passive"))
    )
    (net (code "27") (name "Net-(D103-Pad1)") (class "Default")
      (node (ref "D103") (pin "1") (pinfunction "1_1") (pintype "passive"))
      (node (ref "R103") (pin "2") (pinfunction "2_2") (pintype "passive"))
    )
    (net (code "28") (name "Net-(D104-Pad1)") (class "Default")
      (node (ref "D104") (pin "1") (pinfunction "1_1") (pintype "passive"))
      (node (ref "R104") (pin "2") (pinfunction "2_2") (pintype "passive"))
    )
    (net (code "29") (name "Net-(D106-Pad1)") (class "Default")
      (node (ref "D106") (pin "1") (pinfunction "1_1") (pintype "passive"))
      (node (ref "R115") (pin "2") (pinfunction "2_2") (pintype "passive"))
    )
    (net (code "30") (name "Net-(D107-Pad1)") (class "Default")
      (node (ref "D107") (pin "1") (pinfunction "1_1") (pintype "passive"))
      (node (ref "R109") (pin "2") (pinfunction "2_2") (pintype "passive"))
    )
    (net (code "31") (name "Net-(D107-Pad2)") (class "Default")
      (node (ref "D107") (pin "2") (pinfunction "2_2") (pintype "passive"))
      (node (ref "V100") (pin "3") (pinfunction "3_3") (pintype "passive"))
    )
    (net (code "32") (name "Net-(D108-Pad2)") (class "Default")
      (node (ref "D108") (pin "2") (pinfunction "2_2") (pintype "passive"))
      (node (ref "R105") (pin "1") (pinfunction "1_1") (pintype "passive"))
    )
    (net (code "33") (name "Net-(D109-Pad2)") (class "Default")
      (node (ref "D109") (pin "2") (pinfunction "2_2") (pintype "passive"))
      (node (ref "R106") (pin "1") (pinfunction "1_1") (pintype "passive"))
    )
    (net (code "34") (name "Net-(D110-Pad2)") (class "Default")
      (node (ref "D110") (pin "2") (pinfunction "2_2") (pintype "passive"))
      (node (ref "R107") (pin "1") (pinfunction "1_1") (pintype "passive"))
    )
    (net (code "35") (name "Net-(D111-Pad2)") (class "Default")
      (node (ref "D111") (pin "2") (pinfunction "2_2") (pintype "passive"))
      (node (ref "R108") (pin "1") (pinfunction "1_1") (pintype "passive"))
    )
    (net (code "36") (name "Net-(D112-Pad1)") (class "Default")
      (node (ref "D112") (pin "1") (pinfunction "1_1") (pintype "passive"))
      (node (ref "R113") (pin "2") (pinfunction "2_2") (pintype "passive"))
    )
    (net (code "37") (name "Net-(D112-Pad2)") (class "Default")
      (node (ref "D112") (pin "2") (pinfunction "2_2") (pintype "passive"))
      (node (ref "V101") (pin "3") (pinfunction "3_3") (pintype "passive"))
    )
    (net (code "38") (name "Net-(G100-Out)") (class "Default")
      (node (ref "C100") (pin "2") (pinfunction "2_2") (pintype "passive"))
      (node (ref "G100") (pin "3") (pinfunction "Out_3") (pintype "passive"))
    )
    (net (code "39") (name "Net-(U100-(XIN0)PA14)") (class "Default")
      (node (ref "C100") (pin "1") (pinfunction "1_1") (pintype "passive"))
      (node (ref "U100") (pin "31") (pinfunction "(XIN0)PA14_31") (pintype "bidirectional"))
    )
    (net (code "40") (name "Net-(U100-PA06{slash}AIN0_6{slash}COM0_2)") (class "Default")
      (node (ref "R117") (pin "1") (pinfunction "1_1") (pintype "passive"))
      (node (ref "U100") (pin "15") (pinfunction "PA06/AIN0_6/COM0_2_15") (pintype "bidirectional"))
    )
    (net (code "41") (name "Net-(U100-PA07{slash}AIN0_7{slash}COM0_3)") (class "Default")
      (node (ref "R116") (pin "1") (pinfunction "1_1") (pintype "passive"))
      (node (ref "U100") (pin "16") (pinfunction "PA07/AIN0_7/COM0_3_16") (pintype "bidirectional"))
    )
    (net (code "42") (name "Net-(U100-PA08{slash}AIN0_8{slash}AIN1_2{slash}COM0_0{slash}COM2_1)") (class "Default")
      (node (ref "U100") (pin "17") (pinfunction "PA08/AIN0_8/AIN1_2/COM0_0/COM2_1_17") (pintype "bidirectional"))
      (node (ref "X101") (pin "2") (pinfunction "2_2") (pintype "passive"))
    )
    (net (code "43") (name "Net-(U100-PA09{slash}AIN0_9{slash}AIN1_3{slash}COM0_1{slash}COM2_0)") (class "Default")
      (node (ref "U100") (pin "18") (pinfunction "PA09/AIN0_9/AIN1_3/COM0_1/COM2_0_18") (pintype "bidirectional"))
      (node (ref "X101") (pin "3") (pinfunction "3_3") (pintype "passive"))
    )
    (net (code "44") (name "Net-(U100-PA18{slash}COM1_2{slash}COM3_2)") (class "Default")
      (node (ref "D101") (pin "2") (pinfunction "2_2") (pintype "passive"))
      (node (ref "U100") (pin "37") (pinfunction "PA18/COM1_2/COM3_2_37") (pintype "bidirectional"))
    )
    (net (code "45") (name "Net-(U100-PA19{slash}COM1_3{slash}COM3_3)") (class "Default")
      (node (ref "D102") (pin "2") (pinfunction "2_2") (pintype "passive"))
      (node (ref "U100") (pin "38") (pinfunction "PA19/COM1_3/COM3_3_38") (pintype "bidirectional"))
    )
    (net (code "46") (name "Net-(U100-PB00{slash}AIN0_12{slash}COM5_2)") (class "Default")
      (node (ref "R105") (pin "2") (pinfunction "2_2") (pintype "passive"))
      (node (ref "U100") (pin "61") (pinfunction "PB00/AIN0_12/COM5_2_61") (pintype "bidirectional"))
    )
    (net (code "47") (name "Net-(U100-PB01{slash}AIN0_13{slash}COM5_3)") (class "Default")
      (node (ref "R106") (pin "2") (pinfunction "2_2") (pintype "passive"))
      (node (ref "U100") (pin "62") (pinfunction "PB01/AIN0_13/COM5_3_62") (pintype "bidirectional"))
    )
    (net (code "48") (name "Net-(U100-PB02{slash}AIN0_14{slash}COM5_0)") (class "Default")
      (node (ref "R107") (pin "2") (pinfunction "2_2") (pintype "passive"))
      (node (ref "U100") (pin "63") (pinfunction "PB02/AIN0_14/COM5_0_63") (pintype "bidirectional"))
    )
    (net (code "49") (name "Net-(U100-PB03{slash}AIN0_15{slash}COM5_1)") (class "Default")
      (node (ref "R108") (pin "2") (pinfunction "2_2") (pintype "passive"))
      (node (ref "U100") (pin "64") (pinfunction "PB03/AIN0_15/COM5_1_64") (pintype "bidirectional"))
    )
    (net (code "50") (name "Net-(U100-PB16{slash}COM5_0)") (class "Default")
      (node (ref "D103") (pin "2") (pinfunction "2_2") (pintype "passive"))
      (node (ref "U100") (pin "39") (pinfunction "PB16/COM5_0_39") (pintype "bidirectional"))
    )
    (net (code "51") (name "Net-(U100-PB17{slash}COM5_1)") (class "Default")
      (node (ref "D104") (pin "2") (pinfunction "2_2") (pintype "passive"))
      (node (ref "U100") (pin "40") (pinfunction "PB17/COM5_1_40") (pintype "bidirectional"))
    )
    (net (code "52") (name "Net-(U100-VDDCORE)") (class "Default")
      (node (ref "C115") (pin "2") (pinfunction "2_2") (pintype "passive"))
      (node (ref "C116") (pin "2") (pinfunction "2_2") (pintype "passive"))
      (node (ref "U100") (pin "53") (pinfunction "VDDCORE_53") (pintype "passive"))
    )
    (net (code "53") (name "Net-(U102-+Vin)") (class "Default")
      (node (ref "L103") (pin "2") (pinfunction "2_2") (pintype "passive"))
      (node (ref "U102") (pin "1") (pinfunction "+Vin_1") (pintype "power_in"))
    )
    (net (code "54") (name "Net-(U102-+Vout)") (class "Default")
      (node (ref "L102") (pin "1") (pinfunction "1_1") (pintype "passive"))
      (node (ref "U102") (pin "6") (pinfunction "+Vout_6") (pintype "power_in"))
    )
    (net (code "55") (name "Net-(U103-RxD)") (class "Default")
      (node (ref "R118") (pin "2") (pinfunction "2_2") (pintype "passive"))
      (node (ref "U103") (pin "1") (pinfunction "RxD_1") (pintype "open_collector"))
      (node (ref "U104") (pin "7") (pinfunction "INA_7") (pintype "input"))
    )
    (net (code "56") (name "Net-(U103-TxD)") (class "Default")
      (node (ref "U103") (pin "4") (pinfunction "TxD_4") (pintype "input"))
      (node (ref "U104") (pin "6") (pinfunction "OUTB_6") (pintype "output"))
    )
    (net (code "57") (name "Net-(U105-RxD)") (class "Default")
      (node (ref "R119") (pin "2") (pinfunction "2_2") (pintype "passive"))
      (node (ref "U105") (pin "1") (pinfunction "RxD_1") (pintype "open_collector"))
      (node (ref "U106") (pin "7") (pinfunction "INA_7") (pintype "input"))
    )
    (net (code "58") (name "Net-(U105-TxD)") (class "Default")
      (node (ref "U105") (pin "4") (pinfunction "TxD_4") (pintype "input"))
      (node (ref "U106") (pin "6") (pinfunction "OUTB_6") (pintype "output"))
    )
    (net (code "59") (name "Net-(U107-A)") (class "Default")
      (node (ref "R110") (pin "2") (pinfunction "2_2") (pintype "passive"))
      (node (ref "U107") (pin "1") (pinfunction "A_1") (pintype "passive"))
    )
    (net (code "60") (name "Net-(U107-C-Pad4)") (class "Default")
      (node (ref "U107") (pin "4") (pinfunction "C_4") (pintype "passive"))
      (node (ref "V100") (pin "1") (pinfunction "1_1") (pintype "passive"))
    )
    (net (code "61") (name "Net-(U108-A)") (class "Default")
      (node (ref "R114") (pin "2") (pinfunction "2_2") (pintype "passive"))
      (node (ref "U108") (pin "1") (pinfunction "A_1") (pintype "passive"))
    )
    (net (code "62") (name "Net-(U108-C-Pad4)") (class "Default")
      (node (ref "U108") (pin "4") (pinfunction "C_4") (pintype "passive"))
      (node (ref "V101") (pin "1") (pinfunction "1_1") (pintype "passive"))
    )
    (net (code "63") (name "Net-(U109-EN)") (class "Default")
      (node (ref "R122") (pin "1") (pinfunction "1_1") (pintype "passive"))
      (node (ref "U109") (pin "1") (pinfunction "EN_1") (pintype "passive"))
    )
    (net (code "64") (name "Net-(X100-Shield)") (class "Default")
      (node (ref "R100") (pin "2") (pinfunction "2_2") (pintype "passive"))
      (node (ref "X100") (pin "Shell") (pinfunction "Shield_Shell") (pintype "passive"))
    )
    (net (code "65") (name "unconnected-(U100-(XOUT0)PA15-Pad32)") (class "Default")
      (node (ref "U100") (pin "32") (pinfunction "(XOUT0)PA15_32") (pintype "bidirectional"))
    )
    (net (code "66") (name "unconnected-(U100-PA03{slash}AIN0_1{slash}VREFA-Pad4)") (class "Default")
      (node (ref "U100") (pin "4") (pinfunction "PA03/AIN0_1/VREFA_4") (pintype "bidirectional+no_connect"))
    )
    (net (code "67") (name "unconnected-(U100-PA10{slash}AIN0_10{slash}COM0_2{slash}COM2_2-Pad19)") (class "Default")
      (node (ref "U100") (pin "19") (pinfunction "PA10/AIN0_10/COM0_2/COM2_2_19") (pintype "bidirectional+no_connect"))
    )
    (net (code "68") (name "unconnected-(U100-PA11{slash}AIN0_11{slash}COM0_3{slash}COM2_3-Pad20)") (class "Default")
      (node (ref "U100") (pin "20") (pinfunction "PA11/AIN0_11/COM0_3/COM2_3_20") (pintype "bidirectional+no_connect"))
    )
    (net (code "69") (name "unconnected-(U100-PA12{slash}COM2_0{slash}COM4_1-Pad29)") (class "Default")
      (node (ref "U100") (pin "29") (pinfunction "PA12/COM2_0/COM4_1_29") (pintype "bidirectional+no_connect"))
    )
    (net (code "70") (name "unconnected-(U100-PA13{slash}COM2_1{slash}COM4_0-Pad30)") (class "Default")
      (node (ref "U100") (pin "30") (pinfunction "PA13/COM2_1/COM4_0_30") (pintype "bidirectional+no_connect"))
    )
    (net (code "71") (name "unconnected-(U100-PA16{slash}COM1_0{slash}COM3_1-Pad35)") (class "Default")
      (node (ref "U100") (pin "35") (pinfunction "PA16/COM1_0/COM3_1_35") (pintype "bidirectional+no_connect"))
    )
    (net (code "72") (name "unconnected-(U100-PA17{slash}COM1_1{slash}COM3_0-Pad36)") (class "Default")
      (node (ref "U100") (pin "36") (pinfunction "PA17/COM1_1/COM3_0_36") (pintype "bidirectional+no_connect"))
    )
    (net (code "73") (name "unconnected-(U100-PA20{slash}COM5_2{slash}COM3_2-Pad41)") (class "Default")
      (node (ref "U100") (pin "41") (pinfunction "PA20/COM5_2/COM3_2_41") (pintype "bidirectional+no_connect"))
    )
    (net (code "74") (name "unconnected-(U100-PA21{slash}COM5_3{slash}COM3_3-Pad42)") (class "Default")
      (node (ref "U100") (pin "42") (pinfunction "PA21/COM5_3/COM3_3_42") (pintype "bidirectional+no_connect"))
    )
    (net (code "75") (name "unconnected-(U100-PA22{slash}COM5_1{slash}COM3_0{slash}CAN0_TX-Pad43)") (class "Default")
      (node (ref "U100") (pin "43") (pinfunction "PA22/COM5_1/COM3_0/CAN0_TX_43") (pintype "bidirectional+no_connect"))
    )
    (net (code "76") (name "unconnected-(U100-PA23{slash}COM5_0{slash}COM3_1{slash}CAN0_RX-Pad44)") (class "Default")
      (node (ref "U100") (pin "44") (pinfunction "PA23/COM5_0/COM3_1/CAN0_RX_44") (pintype "bidirectional+no_connect"))
    )
    (net (code "77") (name "unconnected-(U100-PA27-Pad51)") (class "Default")
      (node (ref "U100") (pin "51") (pinfunction "PA27_51") (pintype "bidirectional+no_connect"))
    )
    (net (code "78") (name "unconnected-(U100-PB05{slash}AIN1_7-Pad6)") (class "Default")
      (node (ref "U100") (pin "6") (pinfunction "PB05/AIN1_7_6") (pintype "bidirectional+no_connect"))
    )
    (net (code "79") (name "unconnected-(U100-PB06{slash}AIN1_8-Pad9)") (class "Default")
      (node (ref "U100") (pin "9") (pinfunction "PB06/AIN1_8_9") (pintype "bidirectional+no_connect"))
    )
    (net (code "80") (name "unconnected-(U100-PB07{slash}AIN1_9-Pad10)") (class "Default")
      (node (ref "U100") (pin "10") (pinfunction "PB07/AIN1_9_10") (pintype "bidirectional+no_connect"))
    )
    (net (code "81") (name "unconnected-(U100-PB08{slash}AIN0_2{slash}AIN1_0{slash}COM4_0-Pad11)") (class "Default")
      (node (ref "U100") (pin "11") (pinfunction "PB08/AIN0_2/AIN1_0/COM4_0_11") (pintype "bidirectional+no_connect"))
    )
    (net (code "82") (name "unconnected-(U100-PB10{slash}COM4_2-Pad23)") (class "Default")
      (node (ref "U100") (pin "23") (pinfunction "PB10/COM4_2_23") (pintype "bidirectional+no_connect"))
    )
    (net (code "83") (name "unconnected-(U100-PB11{slash}COM4_3-Pad24)") (class "Default")
      (node (ref "U100") (pin "24") (pinfunction "PB11/COM4_3_24") (pintype "bidirectional+no_connect"))
    )
    (net (code "84") (name "unconnected-(U100-PB12{slash}COM4_0{slash}CAN1_TX-Pad25)") (class "Default")
      (node (ref "U100") (pin "25") (pinfunction "PB12/COM4_0/CAN1_TX_25") (pintype "bidirectional+no_connect"))
    )
    (net (code "85") (name "unconnected-(U100-PB13{slash}COM4_1{slash}CAN1_RX-Pad26)") (class "Default")
      (node (ref "U100") (pin "26") (pinfunction "PB13/COM4_1/CAN1_RX_26") (pintype "bidirectional+no_connect"))
    )
    (net (code "86") (name "unconnected-(U100-PB14{slash}COM4_2{slash}CAN1_TX-Pad27)") (class "Default")
      (node (ref "U100") (pin "27") (pinfunction "PB14/COM4_2/CAN1_TX_27") (pintype "bidirectional+no_connect"))
    )
    (net (code "87") (name "unconnected-(U100-PB15{slash}COM4_3{slash}CAN1_RX-Pad28)") (class "Default")
      (node (ref "U100") (pin "28") (pinfunction "PB15/COM4_3/CAN1_RX_28") (pintype "bidirectional+no_connect"))
    )
    (net (code "88") (name "unconnected-(U100-PB22{slash}COM5_2{slash}COM1_2{slash}XIN1-Pad49)") (class "Default")
      (node (ref "U100") (pin "49") (pinfunction "PB22/COM5_2/COM1_2/XIN1_49") (pintype "bidirectional+no_connect"))
    )
    (net (code "89") (name "unconnected-(U100-PB23{slash}COM5_3{slash}COM1_3{slash}XOUT1-Pad50)") (class "Default")
      (node (ref "U100") (pin "50") (pinfunction "PB23/COM5_3/COM1_3/XOUT1_50") (pintype "bidirectional+no_connect"))
    )
    (net (code "90") (name "unconnected-(U100-PB30{slash}SWO-Pad59)") (class "Default")
      (node (ref "U100") (pin "59") (pinfunction "PB30/SWO_59") (pintype "bidirectional+no_connect"))
    )
    (net (code "91") (name "unconnected-(U100-PB31{slash}COM5_0{slash}COM7_1-Pad60)") (class "Default")
      (node (ref "U100") (pin "60") (pinfunction "PB31/COM5_0/COM7_1_60") (pintype "bidirectional+no_connect"))
    )
    (net (code "92") (name "unconnected-(U100-VSW-Pad55)") (class "Default")
      (node (ref "U100") (pin "55") (pinfunction "VSW_55") (pintype "passive+no_connect"))
    )
    (net (code "93") (name "unconnected-(U103-NC-Pad3)") (class "Default")
      (node (ref "U103") (pin "3") (pinfunction "NC_3") (pintype "passive+no_connect"))
    )
    (net (code "94") (name "unconnected-(U103-NC-Pad8)") (class "Default")
      (node (ref "U103") (pin "8") (pinfunction "NC_8") (pintype "passive+no_connect"))
    )
    (net (code "95") (name "unconnected-(U105-NC-Pad3)") (class "Default")
      (node (ref "U105") (pin "3") (pinfunction "NC_3") (pintype "passive+no_connect"))
    )
    (net (code "96") (name "unconnected-(U105-NC-Pad8)") (class "Default")
      (node (ref "U105") (pin "8") (pinfunction "NC_8") (pintype "passive+no_connect"))
    )
    (net (code "97") (name "unconnected-(X102-Pad1)") (class "Default")
      (node (ref "X102") (pin "1") (pinfunction "1_1") (pintype "passive"))
    )
    (net (code "98") (name "unconnected-(X102-Pad2)") (class "Default")
      (node (ref "X102") (pin "2") (pinfunction "2_2") (pintype "passive"))
    )
    (net (code "99") (name "unconnected-(X102-Pad4)") (class "Default")
      (node (ref "X102") (pin "4") (pinfunction "4_4") (pintype "passive"))
    )
    (net (code "100") (name "unconnected-(X102-Pad5)") (class "Default")
      (node (ref "X102") (pin "5") (pinfunction "5_5") (pintype "passive"))
    )
    (net (code "101") (name "unconnected-(X102-Pad6)") (class "Default")
      (node (ref "X102") (pin "6") (pinfunction "6_6") (pintype "passive"))
    )
    (net (code "102") (name "unconnected-(X102-Pad9)") (class "Default")
      (node (ref "X102") (pin "9") (pinfunction "9_9") (pintype "passive"))
    )
    (net (code "103") (name "unconnected-(X102-PadSH)") (class "Default")
      (node (ref "X102") (pin "SH") (pinfunction "SH_SH") (pintype "passive"))
    )
    (net (code "104") (name "unconnected-(X104-KEY-Pad7)") (class "Default")
      (node (ref "X104") (pin "7") (pinfunction "KEY_7") (pintype "passive"))
    )
    (net (code "105") (name "unconnected-(X104-NC{slash}TDI-Pad8)") (class "Default")
      (node (ref "X104") (pin "8") (pinfunction "NC/TDI_8") (pintype "passive"))
    )
    (net (code "106") (name "unconnected-(X104-SWO{slash}TDO-Pad6)") (class "Default")
      (node (ref "X104") (pin "6") (pinfunction "SWO/TDO_6") (pintype "passive"))
    )
  )
)
